# 12V_Buck_For_5V_3V3.net
KiCad netlist of a schematic drawn in Altium Designer
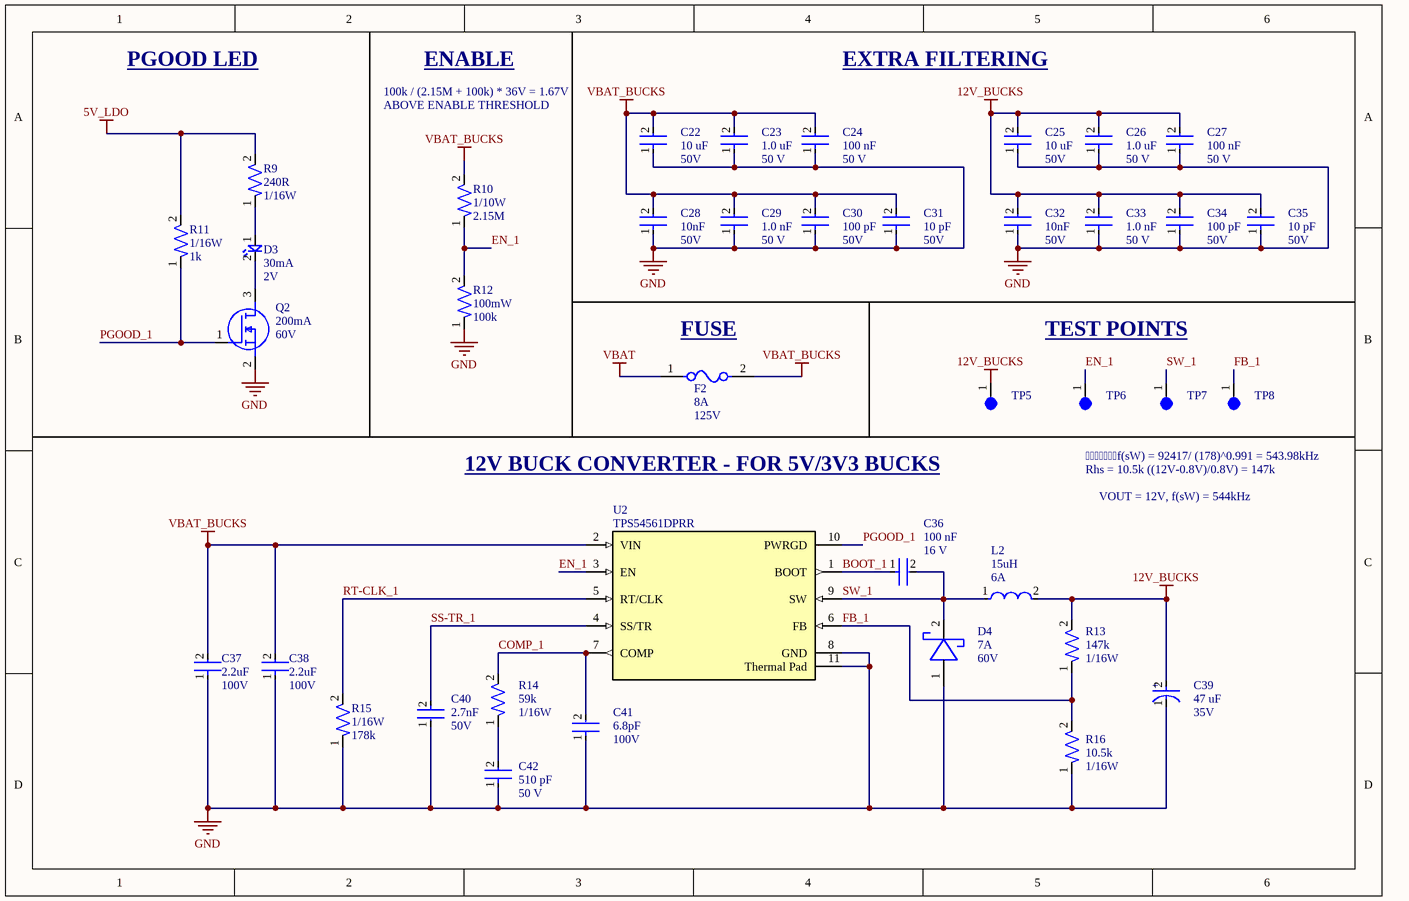
[diagram p0: 12V_Buck_For_5V_3V3.SchDoc]

(export (version "E")
  (design (tool "Eeschema 10.0.6"))
  (components
    (comp (ref "C22")
      (value "CL32B106KBJNNNE")
      (footprint "CAP-1210")
      (description "CAP CER 10UF 50V X7R 1210")
      (fields (field (name "VOLTAGE") "50V") (field (name "CAPACITANCE") "10 uF"))
      (libsource (lib "JLC_25") (part "CAP-10U-0002"))
    )
    (comp (ref "C23")
      (value "CC0805KKX7R9BB105")
      (footprint "CAP-0805")
      (description "CAP CER 1UF 50V X7R 0805")
      (fields (field (name "VOLTAGE") "50 V") (field (name "CAPACITANCE") "1.0 uF"))
      (libsource (lib "JLC_25") (part "CAP-1U-0001"))
    )
    (comp (ref "C24")
      (value "CC0805KRX7R9BB104")
      (footprint "CAP-0805")
      (description "CAP CER 0.1UF 50V X7R 0805")
      (fields (field (name "VOLTAGE RATING") "50 V") (field (name "CAPACITANCE") "100 nF"))
      (libsource (lib "JLC_25") (part "CAP-0.1U-0002"))
    )
    (comp (ref "C25")
      (value "CL32B106KBJNNNE")
      (footprint "CAP-1210")
      (description "CAP CER 10UF 50V X7R 1210")
      (fields (field (name "VOLTAGE") "50V") (field (name "CAPACITANCE") "10 uF"))
      (libsource (lib "JLC_25") (part "CAP-10U-0002"))
    )
    (comp (ref "C26")
      (value "CC0805KKX7R9BB105")
      (footprint "CAP-0805")
      (description "CAP CER 1UF 50V X7R 0805")
      (fields (field (name "VOLTAGE") "50 V") (field (name "CAPACITANCE") "1.0 uF"))
      (libsource (lib "JLC_25") (part "CAP-1U-0001"))
    )
    (comp (ref "C27")
      (value "CC0805KRX7R9BB104")
      (footprint "CAP-0805")
      (description "CAP CER 0.1UF 50V X7R 0805")
      (fields (field (name "VOLTAGE RATING") "50 V") (field (name "CAPACITANCE") "100 nF"))
      (libsource (lib "JLC_25") (part "CAP-0.1U-0002"))
    )
    (comp (ref "C28")
      (value "GRM2195C1H103JA01D")
      (footprint "CAP-0805")
      (description "CAP CER 10000PF 50V C0G/NP0 0805")
      (fields (field (name "VOLTAGE") "50V") (field (name "CAPACITANCE") "10nF"))
      (libsource (lib "JLC_25") (part "CAP-10N-0001"))
    )
    (comp (ref "C29")
      (value "CC0402KRX7R9BB102")
      (footprint "CAP-0402")
      (description "CAP CER 1000PF 50V X7R 0402")
      (fields (field (name "VOLTAGE") "50 V") (field (name "CAPACITANCE") "1.0 nF"))
      (libsource (lib "JLC_25") (part "CAP-1N-0001"))
    )
    (comp (ref "C30")
      (value "CC0402JRNPO9BN101")
      (footprint "CAP-0402")
      (description "CAP CER 100PF 50V C0G/NPO 0402")
      (fields (field (name "CAPACITANCE") "100 pF") (field (name "VOLTAGE") "50V"))
      (libsource (lib "JLC_25") (part "CAP-100P-0001"))
    )
    (comp (ref "C31")
      (value "CC0402JRNPO9BN100")
      (footprint "CAP-0402")
      (description "CAP CER 10PF 50V C0G/NPO 0402")
      (fields (field (name "CAPACITANCE") "10 pF") (field (name "VOLTAGE") "50V"))
      (libsource (lib "JLC_25") (part "CAP-10P-0001"))
    )
    (comp (ref "C32")
      (value "GRM2195C1H103JA01D")
      (footprint "CAP-0805")
      (description "CAP CER 10000PF 50V C0G/NP0 0805")
      (fields (field (name "VOLTAGE") "50V") (field (name "CAPACITANCE") "10nF"))
      (libsource (lib "JLC_25") (part "CAP-10N-0001"))
    )
    (comp (ref "C33")
      (value "CC0402KRX7R9BB102")
      (footprint "CAP-0402")
      (description "CAP CER 1000PF 50V X7R 0402")
      (fields (field (name "VOLTAGE") "50 V") (field (name "CAPACITANCE") "1.0 nF"))
      (libsource (lib "JLC_25") (part "CAP-1N-0001"))
    )
    (comp (ref "C34")
      (value "CC0402JRNPO9BN101")
      (footprint "CAP-0402")
      (description "CAP CER 100PF 50V C0G/NPO 0402")
      (fields (field (name "CAPACITANCE") "100 pF") (field (name "VOLTAGE") "50V"))
      (libsource (lib "JLC_25") (part "CAP-100P-0001"))
    )
    (comp (ref "C35")
      (value "CC0402JRNPO9BN100")
      (footprint "CAP-0402")
      (description "CAP CER 10PF 50V C0G/NPO 0402")
      (fields (field (name "CAPACITANCE") "10 pF") (field (name "VOLTAGE") "50V"))
      (libsource (lib "JLC_25") (part "CAP-10P-0001"))
    )
    (comp (ref "C36")
      (value "CC0402KRX7R7BB104")
      (footprint "CAP-0402")
      (description "CAP CER 0.1UF 16V X7R 0402")
      (fields (field (name "VOLTAGE RATING") "16 V") (field (name "CAPACITANCE") "100 nF"))
      (libsource (lib "JLC_25") (part "CAP-0.1U-0001"))
    )
    (comp (ref "C37")
      (value "CC1206KKX7R0BB225")
      (footprint "CAP-1206")
      (description "CAP CER 2.2UF 100V X7R 1206")
      (fields (field (name "CAPACITANCE") "2.2uF") (field (name "VOLTAGE") "100V"))
      (libsource (lib "JLC_25") (part "CAP-2.2U-0001"))
    )
    (comp (ref "C38")
      (value "CC1206KKX7R0BB225")
      (footprint "CAP-1206")
      (description "CAP CER 2.2UF 100V X7R 1206")
      (fields (field (name "CAPACITANCE") "2.2uF") (field (name "VOLTAGE") "100V"))
      (libsource (lib "JLC_25") (part "CAP-2.2U-0001"))
    )
    (comp (ref "C39")
      (value "EEH-ZC1V470P")
      (footprint "CAP_EEHZC1V470P")
      (description "47 µF 35 V Aluminum - Polymer Capacitors Radial, Can - SMD 60mOhm 4000 Hrs @ 125°C")
      (fields (field (name "VOLTAGE") "35V") (field (name "CAPACITANCE") "47 uF"))
      (libsource (lib "JLC_25") (part "CAP-47U-0003"))
    )
    (comp (ref "C40")
      (value "GRM2165C1H272JA01D")
      (footprint "CAP-0805")
      (description "CAP CER 2700PF 50V C0G/NP0 0805")
      (fields (field (name "VOLTAGE") "50V") (field (name "CAPACITANCE") "2.7nF"))
      (libsource (lib "JLC_25") (part "CAP-2.7N-0001"))
    )
    (comp (ref "C41")
      (value "CC0603CRNPO0BN6R8")
      (footprint "CAP-0603")
      (description "CAP CER 6.8PF 100V C0G/NPO 0603")
      (fields (field (name "VOLTAGE") "100V") (field (name "CAPACITANCE") "6.8pF"))
      (libsource (lib "JLC_25") (part "CAP-6.8P-0001"))
    )
    (comp (ref "C42")
      (value "0402N511J500CT")
      (footprint "CAP-0402")
      (description "CAP CER 510PF 50V C0G/NP0 0402")
      (fields (field (name "VOLTAGE") "50 V") (field (name "CAPACITANCE") "510 pF"))
      (libsource (lib "JLC_25") (part "CAP-510P-0001"))
    )
    (comp (ref "D3")
      (value "BL-HKC36G-AV-TRB")
      (footprint "LED-0603")
      (description "LED YELLOW CLEAR 0603 SMD")
      (fields (field (name "FORWARD CURRENT") "30mA") (field (name "FORWARD VOLTAGE") "2V"))
      (libsource (lib "JLC_25") (part "LED-0001"))
    )
    (comp (ref "D4")
      (value "PDS760-13")
      (footprint "DO-POWERDI5")
      (description "DIODE SCHOTTKY 60V 7A POWERDI5")
      (fields (field (name "FORWARD CURRENT") "7A") (field (name "REVERSE VOLTAGE (DC)") "60V"))
      (libsource (lib "JLC_25") (part "DIO-SCHOTTKY-0001"))
    )
    (comp (ref "F2")
      (value "01550900M")
      (footprint "FUSE-0001")
      (description "FUSE BLOK CARTRIDGE 125V 10A SMD")
      (fields (field (name "FUSE CURRENT") "8A") (field (name "VOLTAGE RATING") "125V"))
      (libsource (lib "JLC_25") (part "FUSE-0001"))
    )
    (comp (ref "L2")
      (value "CSAD1010-150M")
      (footprint "IND-15U-0002")
      (description "SMD MOLDING POWER CHOKE")
      (fields (field (name "INDUCTANCE") "15uH") (field (name "CURRENT RATING") "6A"))
      (libsource (lib "JLC_25") (part "IND-15U-0002-NoJLC"))
    )
    (comp (ref "Q2")
      (value "T2N7002AK,LM")
      (footprint "IC-SOT23-3")
      (description "MOSFET N-CH 60V 200MA SOT23")
      (fields (field (name "CONTINUOUS CURRENT") "200mA") (field (name "VOLTAGE") "60V"))
      (libsource (lib "JLC_25") (part "NMOS-200MA-0001"))
    )
    (comp (ref "R9")
      (value "RC0402FR-07240RL")
      (footprint "RES-0402")
      (description "240R 0.063W 1% 0402 (1005 Metric)  SMD")
      (fields
        (field (name "TOLERANCE") "1%")
        (field (name "RESISTANCE") "240R")
        (field (name "POWER") "1/16W")
      )
      (libsource (lib "JLC_25") (part "RES-240-0001"))
    )
    (comp (ref "R10")
      (value "RC0603FR-072M15L")
      (footprint "RES-0603")
      (description "RES SMD 2.15M OHM 1% 1/10W 0603")
      (fields
        (field (name "TOLERANCE") "1%")
        (field (name "POWER") "1/10W")
        (field (name "RESISTANCE") "2.15M")
      )
      (libsource (lib "JLC_25") (part "RES-2.15M-0001"))
    )
    (comp (ref "R11")
      (value "RC0402FR-071KL")
      (footprint "RES-0402")
      (description "RES 1K OHM 1% 1/16W 0402")
      (fields (field (name "TOLERANCE") "1%") (field (name "POWER") "1/16W") (field (name "RESISTANCE") "1k"))
      (libsource (lib "JLC_25") (part "RES-1k-0001"))
    )
    (comp (ref "R12")
      (value "RC0603FR-07100KL")
      (footprint "RES-0603")
      (description "RES SMD 100K OHM 1% 1/10W 0603")
      (fields
        (field (name "TOLERANCE") "1%")
        (field (name "POWER") "100mW")
        (field (name "RESISTANCE") "100k")
      )
      (libsource (lib "JLC_25") (part "RES-100k-0001"))
    )
    (comp (ref "R13")
      (value "RC0402FR-07147KL")
      (footprint "RES-0402")
      (description "RES 147K OHM 1% 1/16W 0402")
      (fields
        (field (name "TOLERANCE") "1%")
        (field (name "POWER") "1/16W")
        (field (name "RESISTANCE") "147k")
      )
      (libsource (lib "JLC_25") (part "RES-147k-0001"))
    )
    (comp (ref "R14")
      (value "RC0402FR-0759KL")
      (footprint "RES-0402")
      (description "RES 59K OHM 1% 1/16W 0402")
      (fields
        (field (name "TOLERANCE") "1%")
        (field (name "POWER") "1/16W")
        (field (name "RESISTANCE") "59k")
      )
      (libsource (lib "JLC_25") (part "RES-59k-0001"))
    )
    (comp (ref "R15")
      (value "RTT021783FTH")
      (footprint "RES-0402")
      (description "62.5mW Thick Film Resistors 50V ±100ppm/℃ ±1% 178kΩ 0402 Chip Resistor - Surface Mount ROHS")
      (fields
        (field (name "TOLERANCE") "1%")
        (field (name "POWER") "1/16W")
        (field (name "RESISTANCE") "178k")
      )
      (libsource (lib "JLC_25") (part "RES-178k-0001_1"))
    )
    (comp (ref "R16")
      (value "RC0402FR-0710K5L")
      (footprint "RES-0402")
      (description "RES 10.5K OHM 1% 1/16W 0402")
      (fields
        (field (name "TOLERANCE") "1%")
        (field (name "POWER") "1/16W")
        (field (name "RESISTANCE") "10.5k")
      )
      (libsource (lib "JLC_25") (part "RES-10.5k-0001"))
    )
    (comp (ref "TP5")
      (value "5003")
      (footprint "TEST-POINT-0001")
      (description "Oranange PC Test Point, Miniature Phoisphor Bronze Silver Plating Through Hole Mounting Type")
      (libsource (lib "*") (part "TEST-POINT-0001"))
    )
    (comp (ref "TP6")
      (value "5003")
      (footprint "TEST-POINT-0001")
      (description "Oranange PC Test Point, Miniature Phoisphor Bronze Silver Plating Through Hole Mounting Type")
      (libsource (lib "*") (part "TEST-POINT-0001"))
    )
    (comp (ref "TP7")
      (value "5003")
      (footprint "TEST-POINT-0001")
      (description "Oranange PC Test Point, Miniature Phoisphor Bronze Silver Plating Through Hole Mounting Type")
      (libsource (lib "*") (part "TEST-POINT-0001"))
    )
    (comp (ref "TP8")
      (value "5003")
      (footprint "TEST-POINT-0001")
      (description "Oranange PC Test Point, Miniature Phoisphor Bronze Silver Plating Through Hole Mounting Type")
      (libsource (lib "*") (part "TEST-POINT-0001"))
    )
    (comp (ref "U2")
      (value "TPS54561DPRR")
      (footprint "IC-10WSON")
      (description "IC REG BUCK ADJ 5A 10WSON")
      (libsource (lib "JLC_25") (part "IC-BUCK-0001"))
    )
  )
  (nets
    (net (code "1") (name "/BOOT_1") (class "Default")
      (node (ref "C36") (pin "1") (pinfunction "1_1") (pintype "passive"))
      (node (ref "U2") (pin "1") (pinfunction "BOOT_1") (pintype "output"))
    )
    (net (code "2") (name "/COMP_1") (class "Default")
      (node (ref "C41") (pin "2") (pinfunction "2_2") (pintype "passive"))
      (node (ref "R14") (pin "2") (pinfunction "2_2") (pintype "passive"))
      (node (ref "U2") (pin "7") (pinfunction "COMP_7") (pintype "output"))
    )
    (net (code "3") (name "/EN_1") (class "Default")
      (node (ref "R10") (pin "1") (pinfunction "1_1") (pintype "passive"))
      (node (ref "R12") (pin "2") (pinfunction "2_2") (pintype "passive"))
      (node (ref "TP6") (pin "1") (pinfunction "0_1") (pintype "passive"))
      (node (ref "U2") (pin "3") (pinfunction "EN_3") (pintype "input"))
    )
    (net (code "4") (name "/FB_1") (class "Default")
      (node (ref "R13") (pin "1") (pinfunction "1_1") (pintype "passive"))
      (node (ref "R16") (pin "2") (pinfunction "2_2") (pintype "passive"))
      (node (ref "TP8") (pin "1") (pinfunction "0_1") (pintype "passive"))
      (node (ref "U2") (pin "6") (pinfunction "FB_6") (pintype "input"))
    )
    (net (code "5") (name "/PGOOD_1") (class "Default")
      (node (ref "Q2") (pin "1") (pinfunction "G_1") (pintype "passive"))
      (node (ref "R11") (pin "1") (pinfunction "1_1") (pintype "passive"))
      (node (ref "U2") (pin "10") (pinfunction "PWRGD_10") (pintype "open_collector"))
    )
    (net (code "6") (name "/RT-CLK_1") (class "Default")
      (node (ref "R15") (pin "2") (pinfunction "2_2") (pintype "passive"))
      (node (ref "U2") (pin "5") (pinfunction "RT/CLK_5") (pintype "input"))
    )
    (net (code "7") (name "/SS-TR_1") (class "Default")
      (node (ref "C40") (pin "2") (pinfunction "2_2") (pintype "passive"))
      (node (ref "U2") (pin "4") (pinfunction "SS/TR_4") (pintype "input"))
    )
    (net (code "8") (name "/SW_1") (class "Default")
      (node (ref "C36") (pin "2") (pinfunction "2_2") (pintype "passive"))
      (node (ref "D4") (pin "2") (pinfunction "ANODE_2") (pintype "passive"))
      (node (ref "L2") (pin "1") (pinfunction "1_1") (pintype "passive"))
      (node (ref "TP7") (pin "1") (pinfunction "0_1") (pintype "passive"))
      (node (ref "U2") (pin "9") (pinfunction "SW_9") (pintype "input"))
    )
    (net (code "9") (name "5V_LDO") (class "Default")
      (node (ref "R11") (pin "2") (pinfunction "2_2") (pintype "passive"))
      (node (ref "R9") (pin "2") (pinfunction "2_2") (pintype "passive"))
    )
    (net (code "10") (name "12V_BUCKS") (class "Default")
      (node (ref "C25") (pin "2") (pinfunction "2_2") (pintype "passive"))
      (node (ref "C26") (pin "2") (pinfunction "2_2") (pintype "passive"))
      (node (ref "C27") (pin "2") (pinfunction "2_2") (pintype "passive"))
      (node (ref "C32") (pin "2") (pinfunction "2_2") (pintype "passive"))
      (node (ref "C33") (pin "2") (pinfunction "2_2") (pintype "passive"))
      (node (ref "C34") (pin "2") (pinfunction "2_2") (pintype "passive"))
      (node (ref "C35") (pin "2") (pinfunction "2_2") (pintype "passive"))
      (node (ref "C39") (pin "2") (pinfunction "A_2") (pintype "passive"))
      (node (ref "L2") (pin "2") (pinfunction "2_2") (pintype "passive"))
      (node (ref "R13") (pin "2") (pinfunction "2_2") (pintype "passive"))
      (node (ref "TP5") (pin "1") (pinfunction "0_1") (pintype "passive"))
    )
    (net (code "11") (name "GND") (class "Default")
      (node (ref "C22") (pin "1") (pinfunction "1_1") (pintype "passive"))
      (node (ref "C23") (pin "1") (pinfunction "1_1") (pintype "passive"))
      (node (ref "C24") (pin "1") (pinfunction "1_1") (pintype "passive"))
      (node (ref "C25") (pin "1") (pinfunction "1_1") (pintype "passive"))
      (node (ref "C26") (pin "1") (pinfunction "1_1") (pintype "passive"))
      (node (ref "C27") (pin "1") (pinfunction "1_1") (pintype "passive"))
      (node (ref "C28") (pin "1") (pinfunction "1_1") (pintype "passive"))
      (node (ref "C29") (pin "1") (pinfunction "1_1") (pintype "passive"))
      (node (ref "C30") (pin "1") (pinfunction "1_1") (pintype "passive"))
      (node (ref "C31") (pin "1") (pinfunction "1_1") (pintype "passive"))
      (node (ref "C32") (pin "1") (pinfunction "1_1") (pintype "passive"))
      (node (ref "C33") (pin "1") (pinfunction "1_1") (pintype "passive"))
      (node (ref "C34") (pin "1") (pinfunction "1_1") (pintype "passive"))
      (node (ref "C35") (pin "1") (pinfunction "1_1") (pintype "passive"))
      (node (ref "C37") (pin "1") (pinfunction "1_1") (pintype "passive"))
      (node (ref "C38") (pin "1") (pinfunction "1_1") (pintype "passive"))
      (node (ref "C39") (pin "1") (pinfunction "C_1") (pintype "passive"))
      (node (ref "C40") (pin "1") (pinfunction "1_1") (pintype "passive"))
      (node (ref "C41") (pin "1") (pinfunction "1_1") (pintype "passive"))
      (node (ref "C42") (pin "1") (pinfunction "1_1") (pintype "passive"))
      (node (ref "D4") (pin "1") (pinfunction "CATHODE_1") (pintype "passive"))
      (node (ref "Q2") (pin "2") (pinfunction "S_2") (pintype "passive"))
      (node (ref "R12") (pin "1") (pinfunction "1_1") (pintype "passive"))
      (node (ref "R15") (pin "1") (pinfunction "1_1") (pintype "passive"))
      (node (ref "R16") (pin "1") (pinfunction "1_1") (pintype "passive"))
      (node (ref "U2") (pin "11") (pinfunction "Thermal_Pad_11") (pintype "power_in"))
      (node (ref "U2") (pin "8") (pinfunction "GND_8") (pintype "power_in"))
    )
    (net (code "12") (name "Net-(C42-Pad2)") (class "Default")
      (node (ref "C42") (pin "2") (pinfunction "2_2") (pintype "passive"))
      (node (ref "R14") (pin "1") (pinfunction "1_1") (pintype "passive"))
    )
    (net (code "13") (name "Net-(D3-Pad1)") (class "Default")
      (node (ref "D3") (pin "1") (pinfunction "1_1") (pintype "passive"))
      (node (ref "R9") (pin "1") (pinfunction "1_1") (pintype "passive"))
    )
    (net (code "14") (name "Net-(Q2-D)") (class "Default")
      (node (ref "D3") (pin "2") (pinfunction "2_2") (pintype "passive"))
      (node (ref "Q2") (pin "3") (pinfunction "D_3") (pintype "passive"))
    )
    (net (code "15") (name "VBAT") (class "Default")
      (node (ref "F2") (pin "1") (pinfunction "1_1") (pintype "passive"))
    )
    (net (code "16") (name "VBAT_BUCKS") (class "Default")
      (node (ref "C22") (pin "2") (pinfunction "2_2") (pintype "passive"))
      (node (ref "C23") (pin "2") (pinfunction "2_2") (pintype "passive"))
      (node (ref "C24") (pin "2") (pinfunction "2_2") (pintype "passive"))
      (node (ref "C28") (pin "2") (pinfunction "2_2") (pintype "passive"))
      (node (ref "C29") (pin "2") (pinfunction "2_2") (pintype "passive"))
      (node (ref "C30") (pin "2") (pinfunction "2_2") (pintype "passive"))
      (node (ref "C31") (pin "2") (pinfunction "2_2") (pintype "passive"))
      (node (ref "C37") (pin "2") (pinfunction "2_2") (pintype "passive"))
      (node (ref "C38") (pin "2") (pinfunction "2_2") (pintype "passive"))
      (node (ref "F2") (pin "2") (pinfunction "2_2") (pintype "passive"))
      (node (ref "R10") (pin "2") (pinfunction "2_2") (pintype "passive"))
      (node (ref "U2") (pin "2") (pinfunction "VIN_2") (pintype "input"))
    )
  )
)
